# STM32H730_PINOUT.net
KiCad netlist of a schematic drawn in Altium Designer
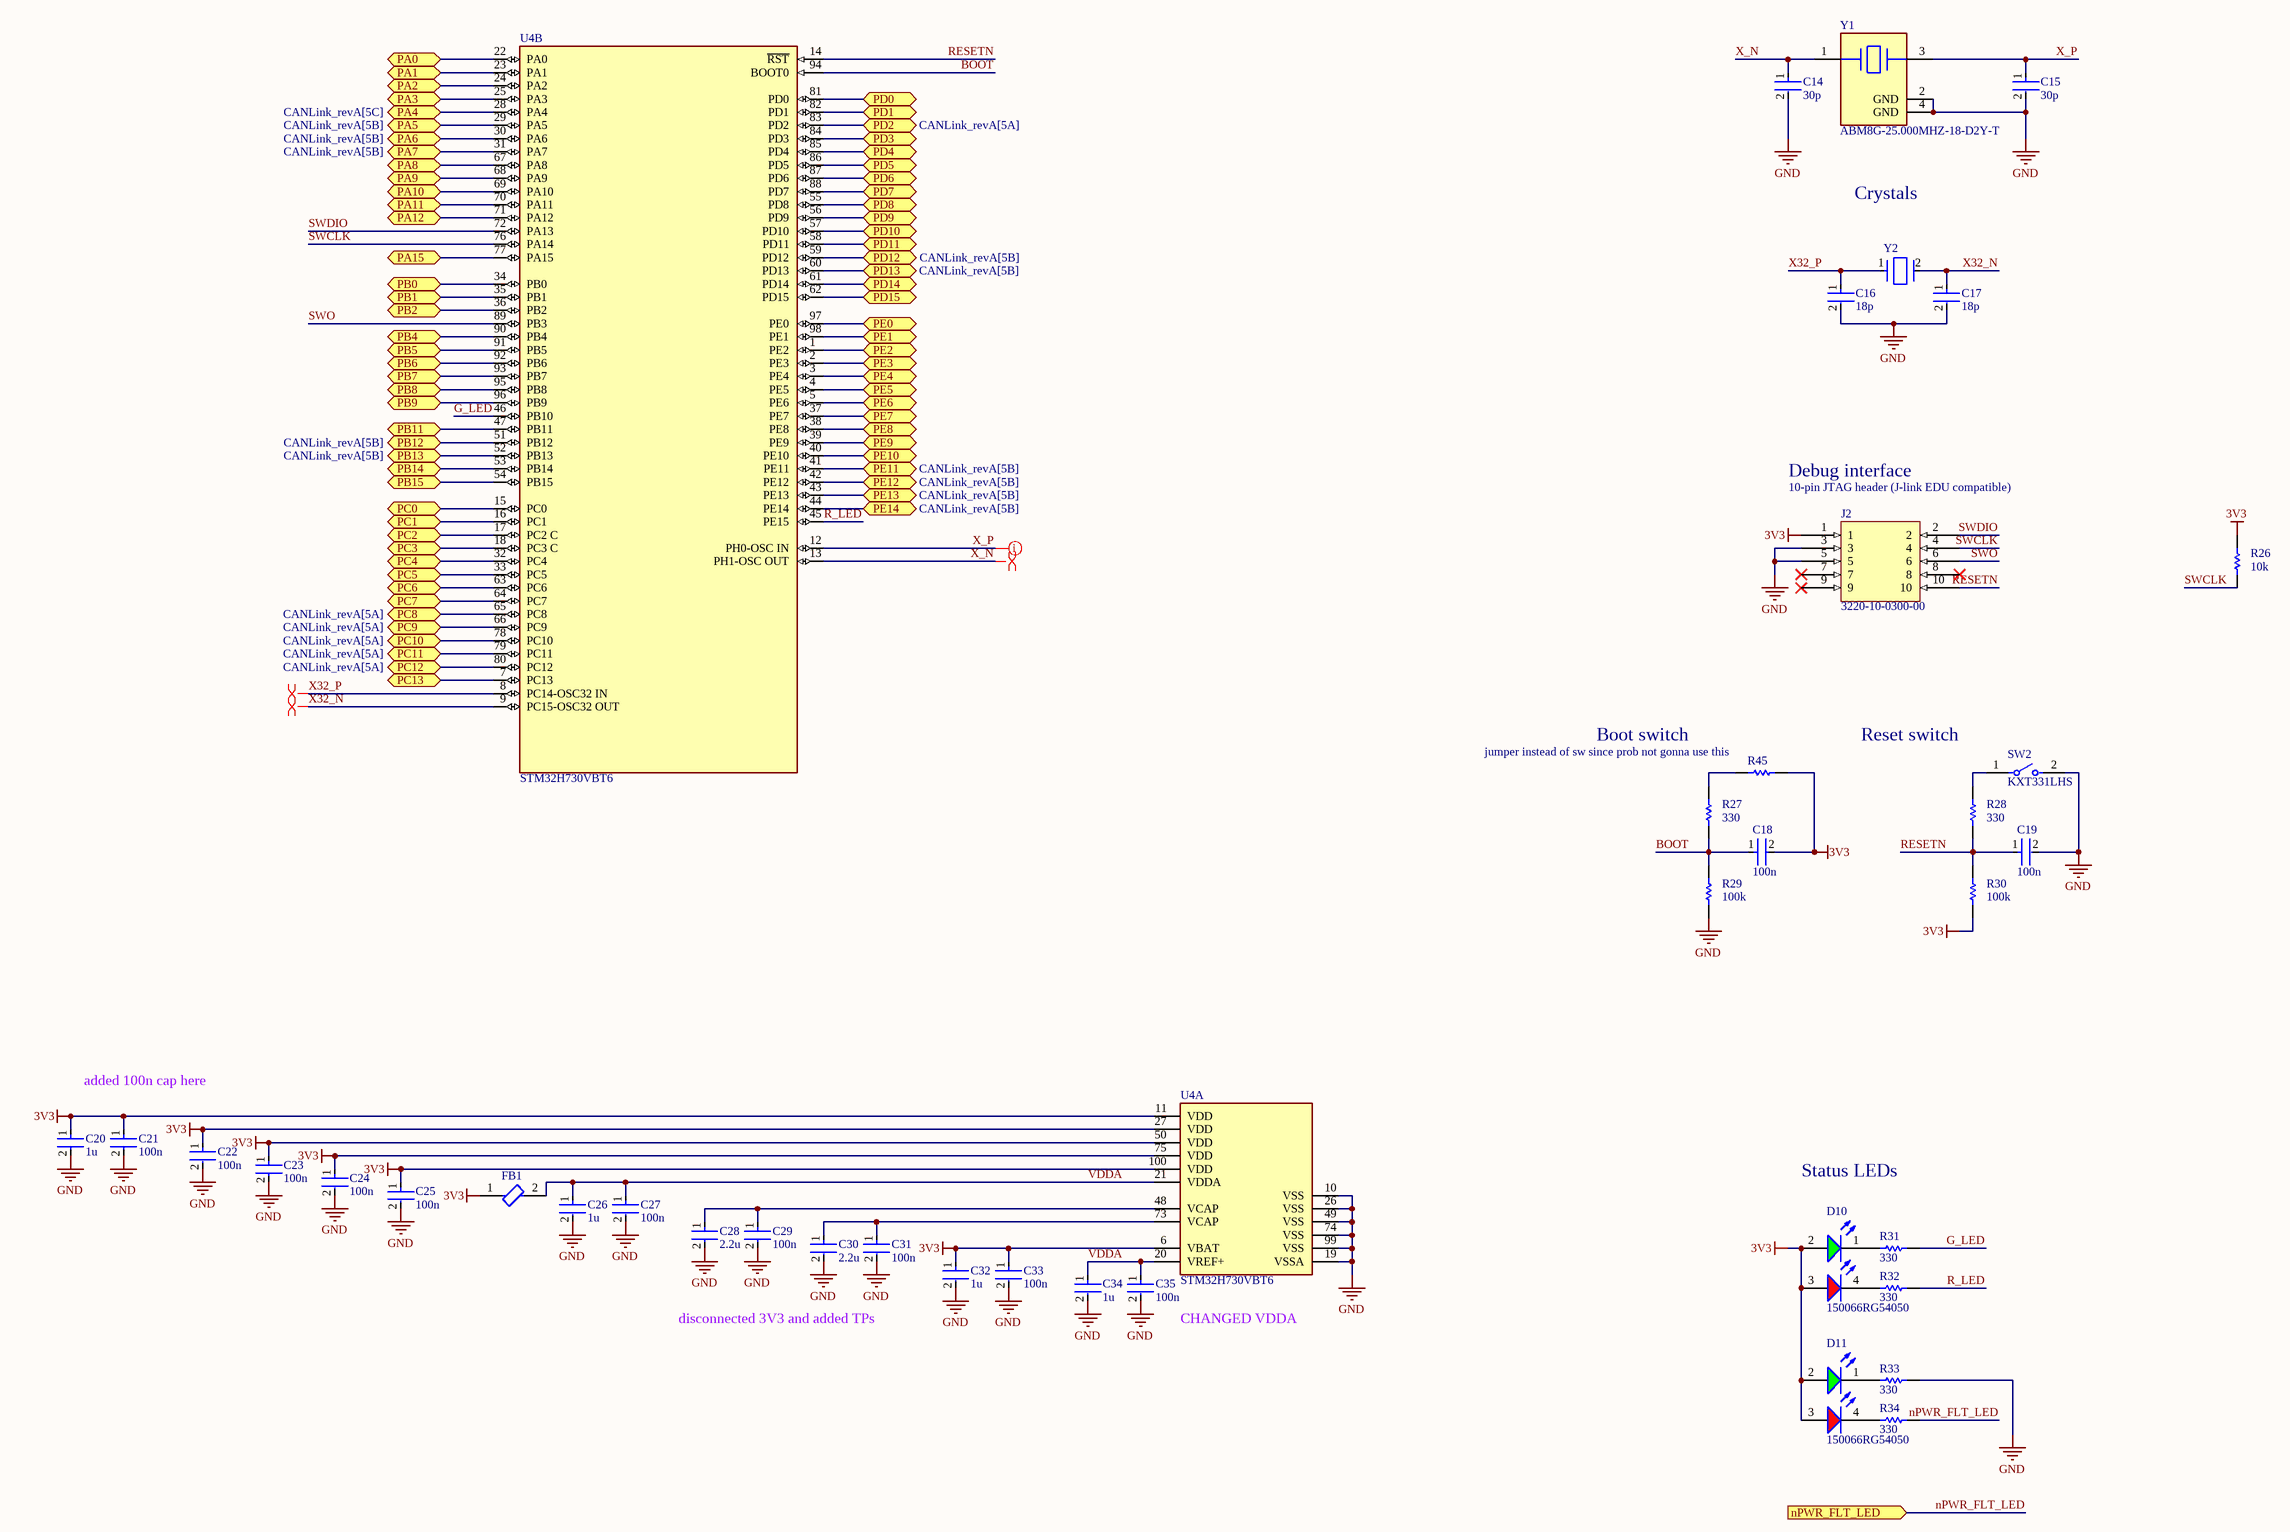
[diagram p0: STM32H730_PINOUT.SchDoc]

(export (version "E")
  (design (tool "Eeschema 10.0.6"))
  (components
    (comp (ref "C14")
      (value "30p")
      (footprint "FP-0402-L_1_0_0_05-W_0_5-IPC_A")
      (description "LARGE PADS, 0402 CAP, CHANGE COMMENT TO MATCH REAL P/N")
      (libsource (lib "Space Concordia") (part "b4654b650e69147ec39a6b967a45e02"))
    )
    (comp (ref "C15")
      (value "30p")
      (footprint "FP-0402-L_1_0_0_05-W_0_5-IPC_A")
      (description "LARGE PADS, 0402 CAP, CHANGE COMMENT TO MATCH REAL P/N")
      (libsource (lib "Space Concordia") (part "b4654b650e69147ec39a6b967a45e02"))
    )
    (comp (ref "C16")
      (value "18p")
      (footprint "FP-0402-L_1_0_0_05-W_0_5-IPC_A")
      (description "LARGE PADS, 0402 CAP, CHANGE COMMENT TO MATCH REAL P/N")
      (libsource (lib "Space Concordia") (part "b4654b650e69147ec39a6b967a45e02"))
    )
    (comp (ref "C17")
      (value "18p")
      (footprint "FP-0402-L_1_0_0_05-W_0_5-IPC_A")
      (description "LARGE PADS, 0402 CAP, CHANGE COMMENT TO MATCH REAL P/N")
      (libsource (lib "Space Concordia") (part "b4654b650e69147ec39a6b967a45e02"))
    )
    (comp (ref "C18")
      (value "100n")
      (footprint "FP-0402-L_1_0_0_05-W_0_5-IPC_A")
      (description "LARGE PADS, 0402 CAP, CHANGE COMMENT TO MATCH REAL P/N")
      (libsource (lib "Space Concordia") (part "b4654b650e69147ec39a6b967a45e02"))
    )
    (comp (ref "C19")
      (value "100n")
      (footprint "FP-0402-L_1_0_0_05-W_0_5-IPC_A")
      (description "LARGE PADS, 0402 CAP, CHANGE COMMENT TO MATCH REAL P/N")
      (libsource (lib "Space Concordia") (part "b4654b650e69147ec39a6b967a45e02"))
    )
    (comp (ref "C20")
      (value "1u")
      (footprint "FP-0402-L_1_0_0_05-W_0_5-IPC_A")
      (description "LARGE PADS, 0402 CAP, CHANGE COMMENT TO MATCH REAL P/N")
      (libsource (lib "Space Concordia") (part "b4654b650e69147ec39a6b967a45e02"))
    )
    (comp (ref "C21")
      (value "100n")
      (footprint "FP-0402-L_1_0_0_05-W_0_5-IPC_A")
      (description "LARGE PADS, 0402 CAP, CHANGE COMMENT TO MATCH REAL P/N")
      (libsource (lib "Space Concordia") (part "b4654b650e69147ec39a6b967a45e02"))
    )
    (comp (ref "C22")
      (value "100n")
      (footprint "FP-0402-L_1_0_0_05-W_0_5-IPC_A")
      (description "LARGE PADS, 0402 CAP, CHANGE COMMENT TO MATCH REAL P/N")
      (libsource (lib "Space Concordia") (part "b4654b650e69147ec39a6b967a45e02"))
    )
    (comp (ref "C23")
      (value "100n")
      (footprint "FP-0402-L_1_0_0_05-W_0_5-IPC_A")
      (description "LARGE PADS, 0402 CAP, CHANGE COMMENT TO MATCH REAL P/N")
      (libsource (lib "Space Concordia") (part "b4654b650e69147ec39a6b967a45e02"))
    )
    (comp (ref "C24")
      (value "100n")
      (footprint "FP-0402-L_1_0_0_05-W_0_5-IPC_A")
      (description "LARGE PADS, 0402 CAP, CHANGE COMMENT TO MATCH REAL P/N")
      (libsource (lib "Space Concordia") (part "b4654b650e69147ec39a6b967a45e02"))
    )
    (comp (ref "C25")
      (value "100n")
      (footprint "FP-0402-L_1_0_0_05-W_0_5-IPC_A")
      (description "LARGE PADS, 0402 CAP, CHANGE COMMENT TO MATCH REAL P/N")
      (libsource (lib "Space Concordia") (part "b4654b650e69147ec39a6b967a45e02"))
    )
    (comp (ref "C26")
      (value "1u")
      (footprint "FP-0402-L_1_0_0_05-W_0_5-IPC_A")
      (description "LARGE PADS, 0402 CAP, CHANGE COMMENT TO MATCH REAL P/N")
      (libsource (lib "Space Concordia") (part "b4654b650e69147ec39a6b967a45e02"))
    )
    (comp (ref "C27")
      (value "100n")
      (footprint "FP-0402-L_1_0_0_05-W_0_5-IPC_A")
      (description "LARGE PADS, 0402 CAP, CHANGE COMMENT TO MATCH REAL P/N")
      (libsource (lib "Space Concordia") (part "b4654b650e69147ec39a6b967a45e02"))
    )
    (comp (ref "C28")
      (value "2.2u")
      (footprint "FP-0402-L_1_0_0_05-W_0_5-IPC_A")
      (description "LARGE PADS, 0402 CAP, CHANGE COMMENT TO MATCH REAL P/N")
      (libsource (lib "Space Concordia") (part "b4654b650e69147ec39a6b967a45e02"))
    )
    (comp (ref "C29")
      (value "100n")
      (footprint "FP-0402-L_1_0_0_05-W_0_5-IPC_A")
      (description "LARGE PADS, 0402 CAP, CHANGE COMMENT TO MATCH REAL P/N")
      (libsource (lib "Space Concordia") (part "b4654b650e69147ec39a6b967a45e02"))
    )
    (comp (ref "C30")
      (value "2.2u")
      (footprint "FP-0402-L_1_0_0_05-W_0_5-IPC_A")
      (description "LARGE PADS, 0402 CAP, CHANGE COMMENT TO MATCH REAL P/N")
      (libsource (lib "Space Concordia") (part "b4654b650e69147ec39a6b967a45e02"))
    )
    (comp (ref "C31")
      (value "100n")
      (footprint "FP-0402-L_1_0_0_05-W_0_5-IPC_A")
      (description "LARGE PADS, 0402 CAP, CHANGE COMMENT TO MATCH REAL P/N")
      (libsource (lib "Space Concordia") (part "b4654b650e69147ec39a6b967a45e02"))
    )
    (comp (ref "C32")
      (value "1u")
      (footprint "FP-0402-L_1_0_0_05-W_0_5-IPC_A")
      (description "LARGE PADS, 0402 CAP, CHANGE COMMENT TO MATCH REAL P/N")
      (libsource (lib "Space Concordia") (part "b4654b650e69147ec39a6b967a45e02"))
    )
    (comp (ref "C33")
      (value "100n")
      (footprint "FP-0402-L_1_0_0_05-W_0_5-IPC_A")
      (description "LARGE PADS, 0402 CAP, CHANGE COMMENT TO MATCH REAL P/N")
      (libsource (lib "Space Concordia") (part "b4654b650e69147ec39a6b967a45e02"))
    )
    (comp (ref "C34")
      (value "1u")
      (footprint "FP-0402-L_1_0_0_05-W_0_5-IPC_A")
      (description "LARGE PADS, 0402 CAP, CHANGE COMMENT TO MATCH REAL P/N")
      (libsource (lib "Space Concordia") (part "b4654b650e69147ec39a6b967a45e02"))
    )
    (comp (ref "C35")
      (value "100n")
      (footprint "FP-0402-L_1_0_0_05-W_0_5-IPC_A")
      (description "LARGE PADS, 0402 CAP, CHANGE COMMENT TO MATCH REAL P/N")
      (libsource (lib "Space Concordia") (part "b4654b650e69147ec39a6b967a45e02"))
    )
    (comp (ref "D10")
      (value "150066RG54050")
      (footprint "WL-SBCD_0606")
      (description "Led, Red/Grn, 180Mcd/230Mcd, 624Nm/525Nm Rohs Compliant: Yes")
      (fields (field (name "SOURCE") "rgled.SchLib"))
      (libsource (lib "Space Concordia") (part "CMP-004-00034-2"))
    )
    (comp (ref "D11")
      (value "150066RG54050")
      (footprint "WL-SBCD_0606")
      (description "Led, Red/Grn, 180Mcd/230Mcd, 624Nm/525Nm Rohs Compliant: Yes")
      (fields (field (name "SOURCE") "rgled.SchLib"))
      (libsource (lib "Space Concordia") (part "CMP-004-00034-2"))
    )
    (comp (ref "FB1")
      (value "BLM15PX601SN1D")
      (footprint "FP-BLM15-0_05-IPC_A")
      (description "Chip Ferrite Bead, 0402, 600Ω @ 100MHz, 0.23Ω, 25%, 900mA")
      (fields (field (name "TOLERANCE") "25%"))
      (libsource (lib "Altium Content Vault") (part "5f30dd21d616792df468990f7003faa"))
    )
    (comp (ref "J2")
      (value "3220-10-0300-00")
      (footprint "3220-10-0300-00-Footprint-1")
      (description "CONN HEADER SMD 10POS 1.27MM")
      (libsource (lib "Space Concordia") (part "3220-10-0300-00"))
    )
    (comp (ref "R26")
      (value "10k")
      (footprint "R0603B")
      (description "Resistor")
      (libsource (lib "Space Concordia") (part "Resistor"))
    )
    (comp (ref "R27")
      (value "330")
      (footprint "R0603B")
      (description "Resistor")
      (libsource (lib "Space Concordia") (part "Resistor"))
    )
    (comp (ref "R28")
      (value "330")
      (footprint "R0603B")
      (description "Resistor")
      (libsource (lib "Space Concordia") (part "Resistor"))
    )
    (comp (ref "R29")
      (value "100k")
      (footprint "R0603B")
      (description "Resistor")
      (libsource (lib "Space Concordia") (part "Resistor"))
    )
    (comp (ref "R30")
      (value "100k")
      (footprint "R0603B")
      (description "Resistor")
      (libsource (lib "Space Concordia") (part "Resistor"))
    )
    (comp (ref "R31")
      (value "330")
      (footprint "R0603B")
      (description "Resistor")
      (libsource (lib "Space Concordia") (part "Resistor"))
    )
    (comp (ref "R32")
      (value "330")
      (footprint "R0603B")
      (description "Resistor")
      (libsource (lib "Space Concordia") (part "Resistor"))
    )
    (comp (ref "R33")
      (value "330")
      (footprint "R0603B")
      (description "Resistor")
      (libsource (lib "Space Concordia") (part "Resistor"))
    )
    (comp (ref "R34")
      (value "330")
      (footprint "R0603B")
      (description "Resistor")
      (libsource (lib "Space Concordia") (part "Resistor"))
    )
    (comp (ref "R45")
      (value "0402 JUMPER")
      (footprint "RESC1005X40X25ML05T05")
      (description "READ THE NAME")
      (libsource (lib "Space Concordia") (part "CMP-009-00206-2"))
    )
    (comp (ref "SW2")
      (value "KXT331LHS")
      (footprint "FP-KXT331LHS-MFG")
      (description "SWITCH TACTILE SPST-NO 0.02A 15V")
      (libsource (lib "Altium Content Vault") (part "bb27bde45df87f1f469753f287ef5ae"))
    )
    (comp (ref "U4")
      (value "STM32H730VBT6")
      (footprint "FP-LQFP100-1L-IPC_C")
      (description "IC MCU 32BIT 128KB FLASH 100LQFP")
      (libsource (lib "Altium Content Vault") (part "44dc6501260a4d92b846760feb66c20"))
    )
    (comp (ref "Y1")
      (value "ABM8G-25.000MHZ-18-D2Y-T")
      (footprint "FP-ABM8G-MFG")
      (description "Crystal 25MHz ±20ppm (Tol) ±30ppm (Stability) 18pF FUND 60Ω 4-Pin SMD T/R")
      (fields (field (name "TOLERANCE") "20ppm"))
      (libsource (lib "Altium Content Vault") (part "48e526d86b7f2615d98721063c72f49"))
    )
    (comp (ref "Y2")
      (value "ECS-.327-12.5-1210-TR")
      (footprint "FP-ECX-1210-MFG")
      (description "CRYSTAL 32.7680KHZ 12.5PF SMD")
      (fields
        (field (name "OCTOPART") "https://octopart.com/ecs-.327-12.5-1210-tr-ecs+international-81221340")
        (field (name "TOLERANCE") "20ppm")
      )
      (libsource (lib "Altium Content Vault") (part "99724985039315a44fd0d1401b84e49"))
    )
  )
  (nets
    (net (code "1") (name "/BOOT") (class "Default")
      (node (ref "C18") (pin "1") (pinfunction "1_1") (pintype "passive"))
      (node (ref "R27") (pin "1") (pinfunction "1_1") (pintype "passive"))
      (node (ref "R29") (pin "2") (pinfunction "2_2") (pintype "passive"))
      (node (ref "U4") (pin "94") (pinfunction "BOOT0_94") (pintype "input"))
    )
    (net (code "2") (name "/G_LED") (class "Default")
      (node (ref "R31") (pin "1") (pinfunction "1_1") (pintype "passive"))
      (node (ref "U4") (pin "46") (pinfunction "PB10_46") (pintype "bidirectional"))
    )
    (net (code "3") (name "/PA0") (class "Default")
      (node (ref "U4") (pin "22") (pinfunction "PA0_22") (pintype "bidirectional"))
    )
    (net (code "4") (name "/PA1") (class "Default")
      (node (ref "U4") (pin "23") (pinfunction "PA1_23") (pintype "bidirectional"))
    )
    (net (code "5") (name "/PA2") (class "Default")
      (node (ref "U4") (pin "24") (pinfunction "PA2_24") (pintype "bidirectional"))
    )
    (net (code "6") (name "/PA3") (class "Default")
      (node (ref "U4") (pin "25") (pinfunction "PA3_25") (pintype "bidirectional"))
    )
    (net (code "7") (name "/PA4") (class "Default")
      (node (ref "U4") (pin "28") (pinfunction "PA4_28") (pintype "bidirectional"))
    )
    (net (code "8") (name "/PA5") (class "Default")
      (node (ref "U4") (pin "29") (pinfunction "PA5_29") (pintype "bidirectional"))
    )
    (net (code "9") (name "/PA6") (class "Default")
      (node (ref "U4") (pin "30") (pinfunction "PA6_30") (pintype "bidirectional"))
    )
    (net (code "10") (name "/PA7") (class "Default")
      (node (ref "U4") (pin "31") (pinfunction "PA7_31") (pintype "bidirectional"))
    )
    (net (code "11") (name "/PA8") (class "Default")
      (node (ref "U4") (pin "67") (pinfunction "PA8_67") (pintype "bidirectional"))
    )
    (net (code "12") (name "/PA9") (class "Default")
      (node (ref "U4") (pin "68") (pinfunction "PA9_68") (pintype "bidirectional"))
    )
    (net (code "13") (name "/PA10") (class "Default")
      (node (ref "U4") (pin "69") (pinfunction "PA10_69") (pintype "bidirectional"))
    )
    (net (code "14") (name "/PA11") (class "Default")
      (node (ref "U4") (pin "70") (pinfunction "PA11_70") (pintype "bidirectional"))
    )
    (net (code "15") (name "/PA12") (class "Default")
      (node (ref "U4") (pin "71") (pinfunction "PA12_71") (pintype "bidirectional"))
    )
    (net (code "16") (name "/PA15") (class "Default")
      (node (ref "U4") (pin "77") (pinfunction "PA15_77") (pintype "bidirectional"))
    )
    (net (code "17") (name "/PB0") (class "Default")
      (node (ref "U4") (pin "34") (pinfunction "PB0_34") (pintype "bidirectional"))
    )
    (net (code "18") (name "/PB1") (class "Default")
      (node (ref "U4") (pin "35") (pinfunction "PB1_35") (pintype "bidirectional"))
    )
    (net (code "19") (name "/PB2") (class "Default")
      (node (ref "U4") (pin "36") (pinfunction "PB2_36") (pintype "bidirectional"))
    )
    (net (code "20") (name "/PB4") (class "Default")
      (node (ref "U4") (pin "90") (pinfunction "PB4_90") (pintype "bidirectional"))
    )
    (net (code "21") (name "/PB5") (class "Default")
      (node (ref "U4") (pin "91") (pinfunction "PB5_91") (pintype "bidirectional"))
    )
    (net (code "22") (name "/PB6") (class "Default")
      (node (ref "U4") (pin "92") (pinfunction "PB6_92") (pintype "bidirectional"))
    )
    (net (code "23") (name "/PB7") (class "Default")
      (node (ref "U4") (pin "93") (pinfunction "PB7_93") (pintype "bidirectional"))
    )
    (net (code "24") (name "/PB8") (class "Default")
      (node (ref "U4") (pin "95") (pinfunction "PB8_95") (pintype "bidirectional"))
    )
    (net (code "25") (name "/PB9") (class "Default")
      (node (ref "U4") (pin "96") (pinfunction "PB9_96") (pintype "bidirectional"))
    )
    (net (code "26") (name "/PB11") (class "Default")
      (node (ref "U4") (pin "47") (pinfunction "PB11_47") (pintype "bidirectional"))
    )
    (net (code "27") (name "/PB12") (class "Default")
      (node (ref "U4") (pin "51") (pinfunction "PB12_51") (pintype "bidirectional"))
    )
    (net (code "28") (name "/PB13") (class "Default")
      (node (ref "U4") (pin "52") (pinfunction "PB13_52") (pintype "bidirectional"))
    )
    (net (code "29") (name "/PB14") (class "Default")
      (node (ref "U4") (pin "53") (pinfunction "PB14_53") (pintype "bidirectional"))
    )
    (net (code "30") (name "/PB15") (class "Default")
      (node (ref "U4") (pin "54") (pinfunction "PB15_54") (pintype "bidirectional"))
    )
    (net (code "31") (name "/PC0") (class "Default")
      (node (ref "U4") (pin "15") (pinfunction "PC0_15") (pintype "bidirectional"))
    )
    (net (code "32") (name "/PC1") (class "Default")
      (node (ref "U4") (pin "16") (pinfunction "PC1_16") (pintype "bidirectional"))
    )
    (net (code "33") (name "/PC2") (class "Default")
      (node (ref "U4") (pin "17") (pinfunction "PC2_C_17") (pintype "bidirectional"))
    )
    (net (code "34") (name "/PC3") (class "Default")
      (node (ref "U4") (pin "18") (pinfunction "PC3_C_18") (pintype "bidirectional"))
    )
    (net (code "35") (name "/PC4") (class "Default")
      (node (ref "U4") (pin "32") (pinfunction "PC4_32") (pintype "bidirectional"))
    )
    (net (code "36") (name "/PC5") (class "Default")
      (node (ref "U4") (pin "33") (pinfunction "PC5_33") (pintype "bidirectional"))
    )
    (net (code "37") (name "/PC6") (class "Default")
      (node (ref "U4") (pin "63") (pinfunction "PC6_63") (pintype "bidirectional"))
    )
    (net (code "38") (name "/PC7") (class "Default")
      (node (ref "U4") (pin "64") (pinfunction "PC7_64") (pintype "bidirectional"))
    )
    (net (code "39") (name "/PC8") (class "Default")
      (node (ref "U4") (pin "65") (pinfunction "PC8_65") (pintype "bidirectional"))
    )
    (net (code "40") (name "/PC9") (class "Default")
      (node (ref "U4") (pin "66") (pinfunction "PC9_66") (pintype "bidirectional"))
    )
    (net (code "41") (name "/PC10") (class "Default")
      (node (ref "U4") (pin "78") (pinfunction "PC10_78") (pintype "bidirectional"))
    )
    (net (code "42") (name "/PC11") (class "Default")
      (node (ref "U4") (pin "79") (pinfunction "PC11_79") (pintype "bidirectional"))
    )
    (net (code "43") (name "/PC12") (class "Default")
      (node (ref "U4") (pin "80") (pinfunction "PC12_80") (pintype "bidirectional"))
    )
    (net (code "44") (name "/PC13") (class "Default")
      (node (ref "U4") (pin "7") (pinfunction "PC13_7") (pintype "bidirectional"))
    )
    (net (code "45") (name "/PD0") (class "Default")
      (node (ref "U4") (pin "81") (pinfunction "PD0_81") (pintype "bidirectional"))
    )
    (net (code "46") (name "/PD1") (class "Default")
      (node (ref "U4") (pin "82") (pinfunction "PD1_82") (pintype "bidirectional"))
    )
    (net (code "47") (name "/PD2") (class "Default")
      (node (ref "U4") (pin "83") (pinfunction "PD2_83") (pintype "bidirectional"))
    )
    (net (code "48") (name "/PD3") (class "Default")
      (node (ref "U4") (pin "84") (pinfunction "PD3_84") (pintype "bidirectional"))
    )
    (net (code "49") (name "/PD4") (class "Default")
      (node (ref "U4") (pin "85") (pinfunction "PD4_85") (pintype "bidirectional"))
    )
    (net (code "50") (name "/PD5") (class "Default")
      (node (ref "U4") (pin "86") (pinfunction "PD5_86") (pintype "bidirectional"))
    )
    (net (code "51") (name "/PD6") (class "Default")
      (node (ref "U4") (pin "87") (pinfunction "PD6_87") (pintype "bidirectional"))
    )
    (net (code "52") (name "/PD7") (class "Default")
      (node (ref "U4") (pin "88") (pinfunction "PD7_88") (pintype "bidirectional"))
    )
    (net (code "53") (name "/PD8") (class "Default")
      (node (ref "U4") (pin "55") (pinfunction "PD8_55") (pintype "bidirectional"))
    )
    (net (code "54") (name "/PD9") (class "Default")
      (node (ref "U4") (pin "56") (pinfunction "PD9_56") (pintype "bidirectional"))
    )
    (net (code "55") (name "/PD10") (class "Default")
      (node (ref "U4") (pin "57") (pinfunction "PD10_57") (pintype "bidirectional"))
    )
    (net (code "56") (name "/PD11") (class "Default")
      (node (ref "U4") (pin "58") (pinfunction "PD11_58") (pintype "bidirectional"))
    )
    (net (code "57") (name "/PD12") (class "Default")
      (node (ref "U4") (pin "59") (pinfunction "PD12_59") (pintype "bidirectional"))
    )
    (net (code "58") (name "/PD13") (class "Default")
      (node (ref "U4") (pin "60") (pinfunction "PD13_60") (pintype "bidirectional"))
    )
    (net (code "59") (name "/PD14") (class "Default")
      (node (ref "U4") (pin "61") (pinfunction "PD14_61") (pintype "bidirectional"))
    )
    (net (code "60") (name "/PD15") (class "Default")
      (node (ref "U4") (pin "62") (pinfunction "PD15_62") (pintype "bidirectional"))
    )
    (net (code "61") (name "/PE0") (class "Default")
      (node (ref "U4") (pin "97") (pinfunction "PE0_97") (pintype "bidirectional"))
    )
    (net (code "62") (name "/PE1") (class "Default")
      (node (ref "U4") (pin "98") (pinfunction "PE1_98") (pintype "bidirectional"))
    )
    (net (code "63") (name "/PE2") (class "Default")
      (node (ref "U4") (pin "1") (pinfunction "PE2_1") (pintype "bidirectional"))
    )
    (net (code "64") (name "/PE3") (class "Default")
      (node (ref "U4") (pin "2") (pinfunction "PE3_2") (pintype "bidirectional"))
    )
    (net (code "65") (name "/PE4") (class "Default")
      (node (ref "U4") (pin "3") (pinfunction "PE4_3") (pintype "bidirectional"))
    )
    (net (code "66") (name "/PE5") (class "Default")
      (node (ref "U4") (pin "4") (pinfunction "PE5_4") (pintype "bidirectional"))
    )
    (net (code "67") (name "/PE6") (class "Default")
      (node (ref "U4") (pin "5") (pinfunction "PE6_5") (pintype "bidirectional"))
    )
    (net (code "68") (name "/PE7") (class "Default")
      (node (ref "U4") (pin "37") (pinfunction "PE7_37") (pintype "bidirectional"))
    )
    (net (code "69") (name "/PE8") (class "Default")
      (node (ref "U4") (pin "38") (pinfunction "PE8_38") (pintype "bidirectional"))
    )
    (net (code "70") (name "/PE9") (class "Default")
      (node (ref "U4") (pin "39") (pinfunction "PE9_39") (pintype "bidirectional"))
    )
    (net (code "71") (name "/PE10") (class "Default")
      (node (ref "U4") (pin "40") (pinfunction "PE10_40") (pintype "bidirectional"))
    )
    (net (code "72") (name "/PE11") (class "Default")
      (node (ref "U4") (pin "41") (pinfunction "PE11_41") (pintype "bidirectional"))
    )
    (net (code "73") (name "/PE12") (class "Default")
      (node (ref "U4") (pin "42") (pinfunction "PE12_42") (pintype "bidirectional"))
    )
    (net (code "74") (name "/PE13") (class "Default")
      (node (ref "U4") (pin "43") (pinfunction "PE13_43") (pintype "bidirectional"))
    )
    (net (code "75") (name "/PE14") (class "Default")
      (node (ref "U4") (pin "44") (pinfunction "PE14_44") (pintype "bidirectional"))
    )
    (net (code "76") (name "/RESETN") (class "Default")
      (node (ref "C19") (pin "1") (pinfunction "1_1") (pintype "passive"))
      (node (ref "J2") (pin "10") (pinfunction "10_10") (pintype "input"))
      (node (ref "R28") (pin "1") (pinfunction "1_1") (pintype "passive"))
      (node (ref "R30") (pin "2") (pinfunction "2_2") (pintype "passive"))
      (node (ref "U4") (pin "14") (pinfunction "~{RST}_14") (pintype "input"))
    )
    (net (code "77") (name "/R_LED") (class "Default")
      (node (ref "R32") (pin "1") (pinfunction "1_1") (pintype "passive"))
      (node (ref "U4") (pin "45") (pinfunction "PE15_45") (pintype "bidirectional"))
    )
    (net (code "78") (name "/SWCLK") (class "Default")
      (node (ref "J2") (pin "4") (pinfunction "4_4") (pintype "input"))
      (node (ref "R26") (pin "1") (pinfunction "1_1") (pintype "passive"))
      (node (ref "U4") (pin "76") (pinfunction "PA14_76") (pintype "bidirectional"))
    )
    (net (code "79") (name "/SWDIO") (class "Default")
      (node (ref "J2") (pin "2") (pinfunction "2_2") (pintype "input"))
      (node (ref "U4") (pin "72") (pinfunction "PA13_72") (pintype "bidirectional"))
    )
    (net (code "80") (name "/SWO") (class "Default")
      (node (ref "J2") (pin "6") (pinfunction "6_6") (pintype "input"))
      (node (ref "U4") (pin "89") (pinfunction "PB3_89") (pintype "bidirectional"))
    )
    (net (code "81") (name "/VDDA") (class "Default")
      (node (ref "C26") (pin "1") (pinfunction "1_1") (pintype "passive"))
      (node (ref "C27") (pin "1") (pinfunction "1_1") (pintype "passive"))
      (node (ref "C34") (pin "1") (pinfunction "1_1") (pintype "passive"))
      (node (ref "C35") (pin "1") (pinfunction "1_1") (pintype "passive"))
      (node (ref "FB1") (pin "2") (pinfunction "2_2") (pintype "passive"))
      (node (ref "U4") (pin "20") (pinfunction "VREF+_20") (pintype "power_in"))
      (node (ref "U4") (pin "21") (pinfunction "VDDA_21") (pintype "power_in"))
    )
    (net (code "82") (name "/X32_N") (class "Default")
      (node (ref "C17") (pin "1") (pinfunction "1_1") (pintype "passive"))
      (node (ref "U4") (pin "9") (pinfunction "PC15-OSC32_OUT_9") (pintype "bidirectional"))
      (node (ref "Y2") (pin "2") (pinfunction "Out/In_2") (pintype "passive"))
    )
    (net (code "83") (name "/X32_P") (class "Default")
      (node (ref "C16") (pin "1") (pinfunction "1_1") (pintype "passive"))
      (node (ref "U4") (pin "8") (pinfunction "PC14-OSC32_IN_8") (pintype "bidirectional"))
      (node (ref "Y2") (pin "1") (pinfunction "In/Out_1") (pintype "passive"))
    )
    (net (code "84") (name "/X_N") (class "Default")
      (node (ref "C14") (pin "1") (pinfunction "1_1") (pintype "passive"))
      (node (ref "U4") (pin "13") (pinfunction "PH1-OSC_OUT_13") (pintype "bidirectional"))
      (node (ref "Y1") (pin "1") (pinfunction "1_1") (pintype "passive"))
    )
    (net (code "85") (name "/X_P") (class "Default")
      (node (ref "C15") (pin "1") (pinfunction "1_1") (pintype "passive"))
      (node (ref "U4") (pin "12") (pinfunction "PH0-OSC_IN_12") (pintype "bidirectional"))
      (node (ref "Y1") (pin "3") (pinfunction "3_3") (pintype "passive"))
    )
    (net (code "86") (name "/nPWR_FLT_LED") (class "Default")
      (node (ref "R34") (pin "1") (pinfunction "1_1") (pintype "passive"))
    )
    (net (code "87") (name "3V3") (class "Default")
      (node (ref "C18") (pin "2") (pinfunction "2_2") (pintype "passive"))
      (node (ref "C20") (pin "1") (pinfunction "1_1") (pintype "passive"))
      (node (ref "C21") (pin "1") (pinfunction "1_1") (pintype "passive"))
      (node (ref "C22") (pin "1") (pinfunction "1_1") (pintype "passive"))
      (node (ref "C23") (pin "1") (pinfunction "1_1") (pintype "passive"))
      (node (ref "C24") (pin "1") (pinfunction "1_1") (pintype "passive"))
      (node (ref "C25") (pin "1") (pinfunction "1_1") (pintype "passive"))
      (node (ref "C32") (pin "1") (pinfunction "1_1") (pintype "passive"))
      (node (ref "C33") (pin "1") (pinfunction "1_1") (pintype "passive"))
      (node (ref "D10") (pin "2") (pinfunction "A_2") (pintype "passive"))
      (node (ref "D10") (pin "3") (pinfunction "A_3") (pintype "passive"))
      (node (ref "D11") (pin "2") (pinfunction "A_2") (pintype "passive"))
      (node (ref "D11") (pin "3") (pinfunction "A_3") (pintype "passive"))
      (node (ref "FB1") (pin "1") (pinfunction "1_1") (pintype "passive"))
      (node (ref "J2") (pin "1") (pinfunction "1_1") (pintype "input"))
      (node (ref "R26") (pin "2") (pinfunction "2_2") (pintype "passive"))
      (node (ref "R30") (pin "1") (pinfunction "1_1") (pintype "passive"))
      (node (ref "R45") (pin "2") (pinfunction "2_2") (pintype "passive"))
      (node (ref "U4") (pin "100") (pinfunction "VDD_100") (pintype "power_in"))
      (node (ref "U4") (pin "11") (pinfunction "VDD_11") (pintype "power_in"))
      (node (ref "U4") (pin "27") (pinfunction "VDD_27") (pintype "power_in"))
      (node (ref "U4") (pin "50") (pinfunction "VDD_50") (pintype "power_in"))
      (node (ref "U4") (pin "6") (pinfunction "VBAT_6") (pintype "power_in"))
      (node (ref "U4") (pin "75") (pinfunction "VDD_75") (pintype "power_in"))
    )
    (net (code "88") (name "GND") (class "Default")
      (node (ref "C14") (pin "2") (pinfunction "2_2") (pintype "passive"))
      (node (ref "C15") (pin "2") (pinfunction "2_2") (pintype "passive"))
      (node (ref "C16") (pin "2") (pinfunction "2_2") (pintype "passive"))
      (node (ref "C17") (pin "2") (pinfunction "2_2") (pintype "passive"))
      (node (ref "C19") (pin "2") (pinfunction "2_2") (pintype "passive"))
      (node (ref "C20") (pin "2") (pinfunction "2_2") (pintype "passive"))
      (node (ref "C21") (pin "2") (pinfunction "2_2") (pintype "passive"))
      (node (ref "C22") (pin "2") (pinfunction "2_2") (pintype "passive"))
      (node (ref "C23") (pin "2") (pinfunction "2_2") (pintype "passive"))
      (node (ref "C24") (pin "2") (pinfunction "2_2") (pintype "passive"))
      (node (ref "C25") (pin "2") (pinfunction "2_2") (pintype "passive"))
      (node (ref "C26") (pin "2") (pinfunction "2_2") (pintype "passive"))
      (node (ref "C27") (pin "2") (pinfunction "2_2") (pintype "passive"))
      (node (ref "C28") (pin "2") (pinfunction "2_2") (pintype "passive"))
      (node (ref "C29") (pin "2") (pinfunction "2_2") (pintype "passive"))
      (node (ref "C30") (pin "2") (pinfunction "2_2") (pintype "passive"))
      (node (ref "C31") (pin "2") (pinfunction "2_2") (pintype "passive"))
      (node (ref "C32") (pin "2") (pinfunction "2_2") (pintype "passive"))
      (node (ref "C33") (pin "2") (pinfunction "2_2") (pintype "passive"))
      (node (ref "C34") (pin "2") (pinfunction "2_2") (pintype "passive"))
      (node (ref "C35") (pin "2") (pinfunction "2_2") (pintype "passive"))
      (node (ref "J2") (pin "3") (pinfunction "3_3") (pintype "input"))
      (node (ref "J2") (pin "5") (pinfunction "5_5") (pintype "input"))
      (node (ref "R29") (pin "1") (pinfunction "1_1") (pintype "passive"))
      (node (ref "R33") (pin "1") (pinfunction "1_1") (pintype "passive"))
      (node (ref "SW2") (pin "2") (pinfunction "2_2") (pintype "passive"))
      (node (ref "U4") (pin "10") (pinfunction "VSS_10") (pintype "power_in"))
      (node (ref "U4") (pin "19") (pinfunction "VSSA_19") (pintype "power_in"))
      (node (ref "U4") (pin "26") (pinfunction "VSS_26") (pintype "power_in"))
      (node (ref "U4") (pin "49") (pinfunction "VSS_49") (pintype "power_in"))
      (node (ref "U4") (pin "74") (pinfunction "VSS_74") (pintype "power_in"))
      (node (ref "U4") (pin "99") (pinfunction "VSS_99") (pintype "power_in"))
      (node (ref "Y1") (pin "2") (pinfunction "GND_2") (pintype "power_in"))
      (node (ref "Y1") (pin "4") (pinfunction "GND_4") (pintype "power_in"))
    )
    (net (code "89") (name "Net-(C28-Pad1)") (class "Default")
      (node (ref "C28") (pin "1") (pinfunction "1_1") (pintype "passive"))
      (node (ref "C29") (pin "1") (pinfunction "1_1") (pintype "passive"))
      (node (ref "U4") (pin "48") (pinfunction "VCAP_48") (pintype "power_in"))
    )
    (net (code "90") (name "Net-(C30-Pad1)") (class "Default")
      (node (ref "C30") (pin "1") (pinfunction "1_1") (pintype "passive"))
      (node (ref "C31") (pin "1") (pinfunction "1_1") (pintype "passive"))
      (node (ref "U4") (pin "73") (pinfunction "VCAP_73") (pintype "power_in"))
    )
    (net (code "91") (name "Net-(D10-K-Pad1)") (class "Default")
      (node (ref "D10") (pin "1") (pinfunction "K_1") (pintype "passive"))
      (node (ref "R31") (pin "2") (pinfunction "2_2") (pintype "passive"))
    )
    (net (code "92") (name "Net-(D10-K-Pad4)") (class "Default")
      (node (ref "D10") (pin "4") (pinfunction "K_4") (pintype "passive"))
      (node (ref "R32") (pin "2") (pinfunction "2_2") (pintype "passive"))
    )
    (net (code "93") (name "Net-(D11-K-Pad1)") (class "Default")
      (node (ref "D11") (pin "1") (pinfunction "K_1") (pintype "passive"))
      (node (ref "R33") (pin "2") (pinfunction "2_2") (pintype "passive"))
    )
    (net (code "94") (name "Net-(D11-K-Pad4)") (class "Default")
      (node (ref "D11") (pin "4") (pinfunction "K_4") (pintype "passive"))
      (node (ref "R34") (pin "2") (pinfunction "2_2") (pintype "passive"))
    )
    (net (code "95") (name "Net-(R27-Pad2)") (class "Default")
      (node (ref "R27") (pin "2") (pinfunction "2_2") (pintype "passive"))
      (node (ref "R45") (pin "1") (pinfunction "1_1") (pintype "passive"))
    )
    (net (code "96") (name "Net-(R28-Pad2)") (class "Default")
      (node (ref "R28") (pin "2") (pinfunction "2_2") (pintype "passive"))
      (node (ref "SW2") (pin "1") (pinfunction "1_1") (pintype "passive"))
    )
    (net (code "97") (name "unconnected-(J2-Pad7)") (class "Default")
      (node (ref "J2") (pin "7") (pinfunction "7_7") (pintype "input+no_connect"))
    )
    (net (code "98") (name "unconnected-(J2-Pad8)") (class "Default")
      (node (ref "J2") (pin "8") (pinfunction "8_8") (pintype "input+no_connect"))
    )
    (net (code "99") (name "unconnected-(J2-Pad9)") (class "Default")
      (node (ref "J2") (pin "9") (pinfunction "9_9") (pintype "input+no_connect"))
    )
  )
)
